# Power_supply.net
KiCad netlist of a schematic drawn in Altium Designer
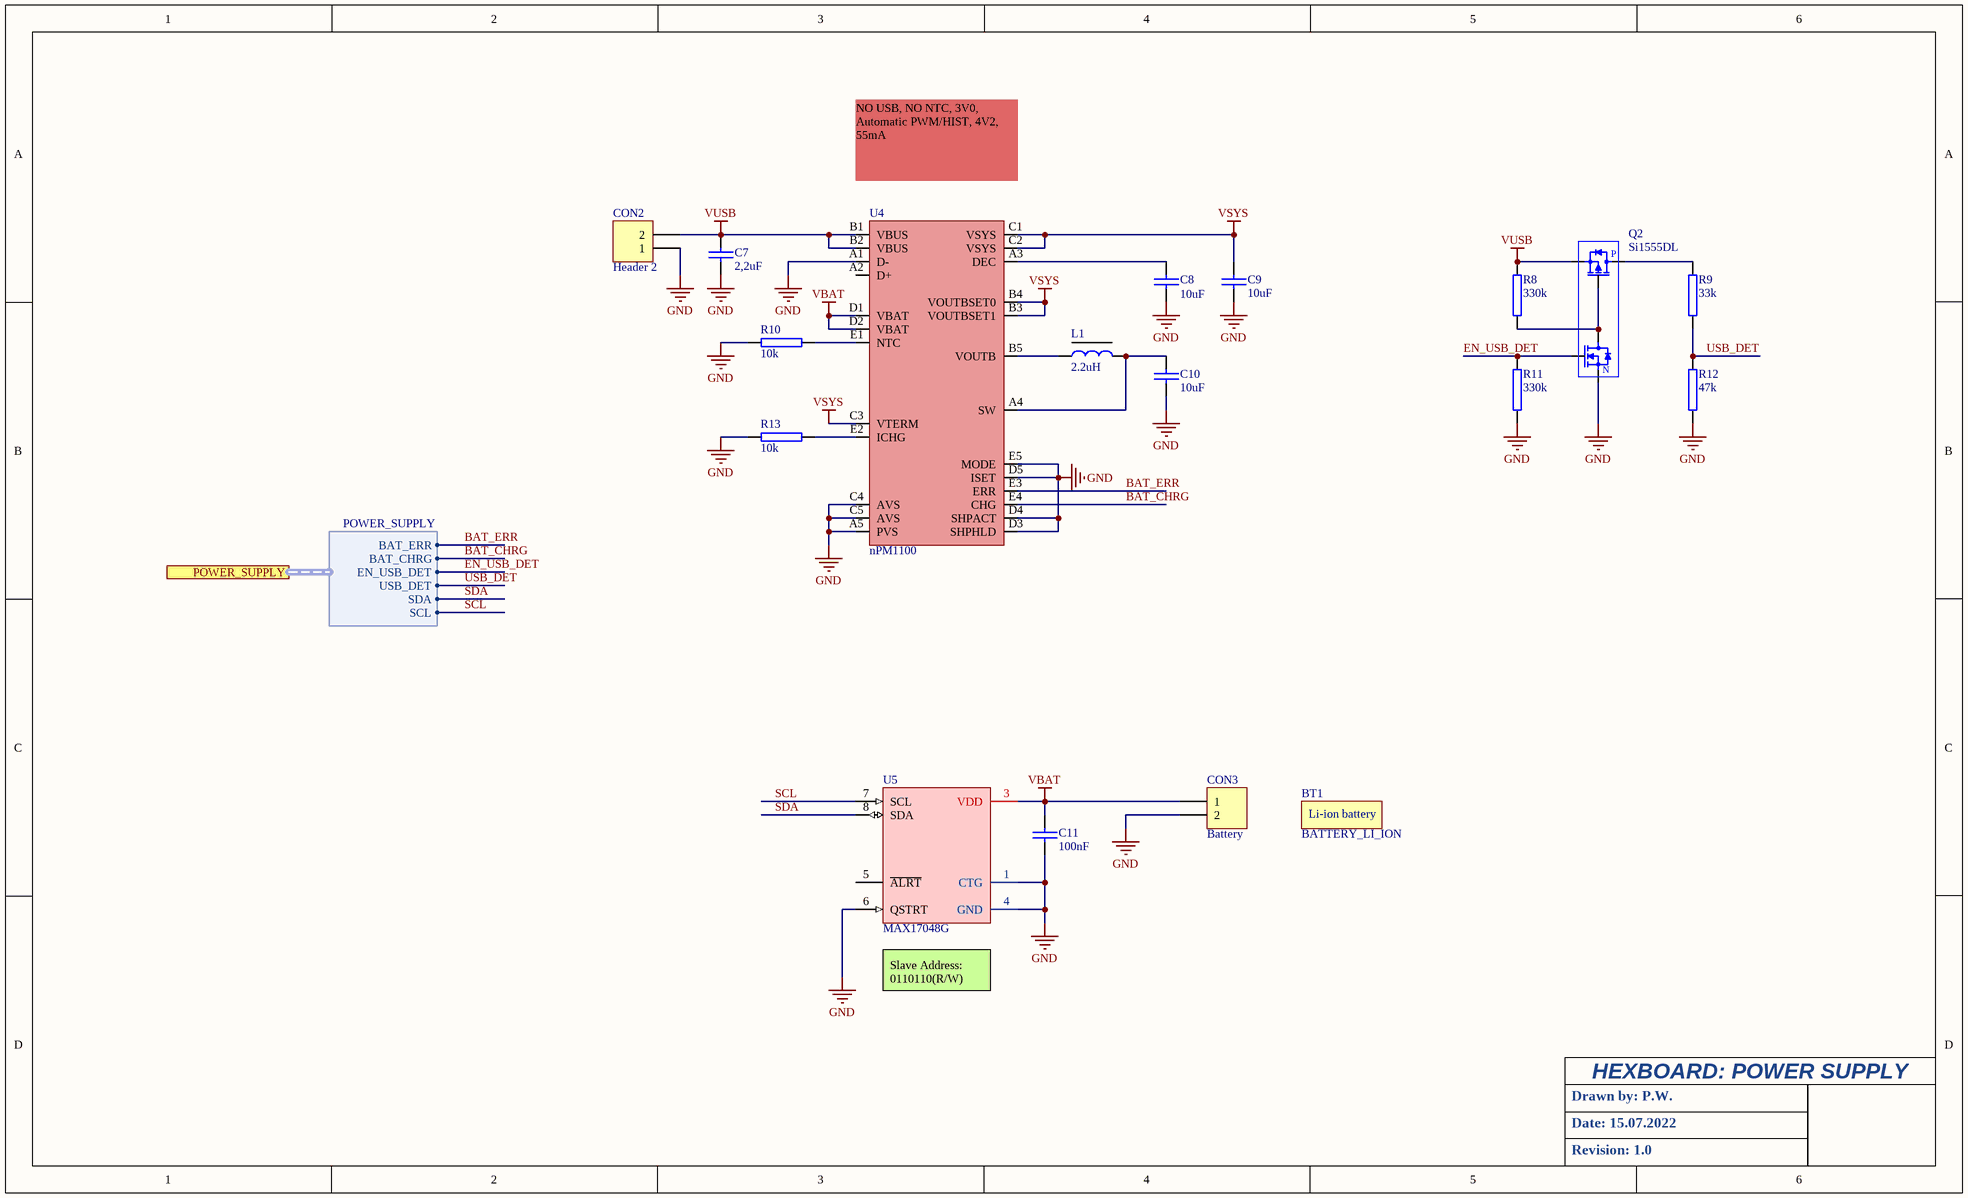
[diagram p0: Power_supply.SchDoc]

(export (version "E")
  (design (tool "Eeschema 10.0.6"))
  (components
    (comp (ref "BT1")
      (value "BATTERY_LI_ION")
      (footprint "LI-ion battery 100mAh")
      (description "Battery")
      (libsource (lib "LIB_PW") (part "BATTERY_LI_ION"))
    )
    (comp (ref "C7")
      (value "2,2uF")
      (footprint "C0603L")
      (description "Capacitor")
      (libsource (lib "LIB_PW") (part "CAP"))
    )
    (comp (ref "C8")
      (value "10uF")
      (footprint "C0603L")
      (description "Capacitor")
      (libsource (lib "LIB_PW") (part "CAP"))
    )
    (comp (ref "C9")
      (value "10uF")
      (footprint "C0603L")
      (description "Capacitor")
      (libsource (lib "LIB_PW") (part "CAP"))
    )
    (comp (ref "C10")
      (value "10uF")
      (footprint "C0603L")
      (description "Capacitor")
      (libsource (lib "LIB_PW") (part "CAP"))
    )
    (comp (ref "C11")
      (value "100nF")
      (footprint "C0603L")
      (description "Capacitor")
      (libsource (lib "LIB_PW") (part "CAP"))
    )
    (comp (ref "CON2")
      (value "Header 2")
      (footprint "HDR1X2")
      (description "Header, 2-Pin")
      (fields (field (name "PUBLISHER") "Altium Limited"))
      (libsource (lib "LIB_PW") (part "Header 2"))
    )
    (comp (ref "CON3")
      (value "Battery")
      (footprint "HDR1X2_1mm27")
      (description "Header, 2-Pin")
      (fields (field (name "PUBLISHER") "Altium Limited"))
      (libsource (lib "") (part "Header 2_1"))
    )
    (comp (ref "L1") (value "2.2uH") (footprint "L0805") (libsource (lib "SCH_PW") (part "INDUCTOR")))
    (comp (ref "Q2") (value "Si1555DL") (footprint "SOT-363") (libsource (lib "LIB_PW") (part "Si1555DL")))
    (comp (ref "R8") (value "330k") (footprint "1608[0603]") (libsource (lib "LIB_PW") (part "RES")))
    (comp (ref "R9") (value "33k") (footprint "1608[0603]") (libsource (lib "LIB_PW") (part "RES")))
    (comp (ref "R10") (value "10k") (footprint "1608[0603]") (libsource (lib "LIB_PW") (part "RES")))
    (comp (ref "R11") (value "330k") (footprint "1608[0603]") (libsource (lib "LIB_PW") (part "RES")))
    (comp (ref "R12") (value "47k") (footprint "1608[0603]") (libsource (lib "LIB_PW") (part "RES")))
    (comp (ref "R13") (value "10k") (footprint "1608[0603]") (libsource (lib "LIB_PW") (part "RES")))
    (comp (ref "U4")
      (value "nPM1100")
      (footprint "BGA25C40P5X5_207X207X52N")
      (description "Integrated Power Managment IC")
      (libsource (lib "LIB_PW") (part "nPM1100"))
    )
    (comp (ref "U5")
      (value "MAX17048G")
      (footprint "TDFN8_2x2x075")
      (description "1-Cell/2-Cell Fuel Gauge with ModelGauge")
      (libsource (lib "LIB_PW") (part "MAX17048G"))
    )
  )
  (nets
    (net (code "2") (name "/BAT_CHRG") (class "Default")
      (node (ref "U4") (pin "E4") (pinfunction "CHG_E4") (pintype "passive"))
    )
    (net (code "3") (name "/BAT_ERR") (class "Default")
      (node (ref "U4") (pin "E3") (pinfunction "ERR_E3") (pintype "passive"))
    )
    (net (code "4") (name "/EN_USB_DET") (class "Default")
      (node (ref "Q2") (pin "2") (pinfunction "G1_2") (pintype "passive"))
      (node (ref "R11") (pin "2") (pinfunction "2_2") (pintype "passive"))
    )
    (net (code "5") (name "/SCL") (class "Default")
      (node (ref "U5") (pin "7") (pinfunction "SCL_7") (pintype "input"))
    )
    (net (code "6") (name "/SDA") (class "Default")
      (node (ref "U5") (pin "8") (pinfunction "SDA_8") (pintype "bidirectional"))
    )
    (net (code "7") (name "/USB_DET") (class "Default")
      (node (ref "R12") (pin "2") (pinfunction "2_2") (pintype "passive"))
      (node (ref "R9") (pin "1") (pinfunction "1_1") (pintype "passive"))
    )
    (net (code "9") (name "GND") (class "Default")
      (node (ref "C10") (pin "2") (pinfunction "2_2") (pintype "passive"))
      (node (ref "C11") (pin "2") (pinfunction "2_2") (pintype "passive"))
      (node (ref "C7") (pin "2") (pinfunction "2_2") (pintype "passive"))
      (node (ref "C8") (pin "2") (pinfunction "2_2") (pintype "passive"))
      (node (ref "C9") (pin "2") (pinfunction "2_2") (pintype "passive"))
      (node (ref "CON2") (pin "1") (pinfunction "1_1") (pintype "passive"))
      (node (ref "CON3") (pin "2") (pinfunction "2_2") (pintype "passive"))
      (node (ref "Q2") (pin "1") (pinfunction "S1_1") (pintype "passive"))
      (node (ref "R10") (pin "2") (pinfunction "2_2") (pintype "passive"))
      (node (ref "R11") (pin "1") (pinfunction "1_1") (pintype "passive"))
      (node (ref "R12") (pin "1") (pinfunction "1_1") (pintype "passive"))
      (node (ref "R13") (pin "2") (pinfunction "2_2") (pintype "passive"))
      (node (ref "U4") (pin "A1") (pinfunction "D-_A1") (pintype "passive"))
      (node (ref "U4") (pin "A5") (pinfunction "PVS_A5") (pintype "passive"))
      (node (ref "U4") (pin "C4") (pinfunction "AVS_C4") (pintype "passive"))
      (node (ref "U4") (pin "C5") (pinfunction "AVS_C5") (pintype "passive"))
      (node (ref "U4") (pin "D3") (pinfunction "SHPHLD_D3") (pintype "passive"))
      (node (ref "U4") (pin "D4") (pinfunction "SHPACT_D4") (pintype "passive"))
      (node (ref "U4") (pin "D5") (pinfunction "ISET_D5") (pintype "passive"))
      (node (ref "U4") (pin "E5") (pinfunction "MODE_E5") (pintype "passive"))
      (node (ref "U5") (pin "1") (pinfunction "CTG_1") (pintype "power_in"))
      (node (ref "U5") (pin "4") (pinfunction "GND_4") (pintype "power_in"))
      (node (ref "U5") (pin "6") (pinfunction "QSTRT_6") (pintype "input"))
    )
    (net (code "10") (name "Net-(Q2-D1)") (class "Default")
      (node (ref "Q2") (pin "5") (pinfunction "G2_5") (pintype "passive"))
      (node (ref "Q2") (pin "6") (pinfunction "D1_6") (pintype "passive"))
      (node (ref "R8") (pin "1") (pinfunction "1_1") (pintype "passive"))
    )
    (net (code "11") (name "Net-(Q2-D2)") (class "Default")
      (node (ref "Q2") (pin "3") (pinfunction "D2_3") (pintype "passive"))
      (node (ref "R9") (pin "2") (pinfunction "2_2") (pintype "passive"))
    )
    (net (code "12") (name "Net-(U4-DEC)") (class "Default")
      (node (ref "C8") (pin "1") (pinfunction "1_1") (pintype "passive"))
      (node (ref "U4") (pin "A3") (pinfunction "DEC_A3") (pintype "passive"))
    )
    (net (code "13") (name "Net-(U4-ICHG)") (class "Default")
      (node (ref "R13") (pin "1") (pinfunction "1_1") (pintype "passive"))
      (node (ref "U4") (pin "E2") (pinfunction "ICHG_E2") (pintype "passive"))
    )
    (net (code "14") (name "Net-(U4-NTC)") (class "Default")
      (node (ref "R10") (pin "1") (pinfunction "1_1") (pintype "passive"))
      (node (ref "U4") (pin "E1") (pinfunction "NTC_E1") (pintype "passive"))
    )
    (net (code "15") (name "Net-(U4-SW)") (class "Default")
      (node (ref "C10") (pin "1") (pinfunction "1_1") (pintype "passive"))
      (node (ref "L1") (pin "2") (pinfunction "2_2") (pintype "passive"))
      (node (ref "U4") (pin "A4") (pinfunction "SW_A4") (pintype "passive"))
    )
    (net (code "16") (name "Net-(U4-VOUTB)") (class "Default")
      (node (ref "L1") (pin "1") (pinfunction "1_1") (pintype "passive"))
      (node (ref "U4") (pin "B5") (pinfunction "VOUTB_B5") (pintype "passive"))
    )
    (net (code "17") (name "VBAT") (class "Default")
      (node (ref "C11") (pin "1") (pinfunction "1_1") (pintype "passive"))
      (node (ref "CON3") (pin "1") (pinfunction "1_1") (pintype "passive"))
      (node (ref "U4") (pin "D1") (pinfunction "VBAT_D1") (pintype "passive"))
      (node (ref "U4") (pin "D2") (pinfunction "VBAT_D2") (pintype "passive"))
      (node (ref "U5") (pin "3") (pinfunction "VDD_3") (pintype "power_in"))
    )
    (net (code "18") (name "VSYS") (class "Default")
      (node (ref "C9") (pin "1") (pinfunction "1_1") (pintype "passive"))
      (node (ref "U4") (pin "B3") (pinfunction "VOUTBSET1_B3") (pintype "passive"))
      (node (ref "U4") (pin "B4") (pinfunction "VOUTBSET0_B4") (pintype "passive"))
      (node (ref "U4") (pin "C1") (pinfunction "VSYS_C1") (pintype "passive"))
      (node (ref "U4") (pin "C2") (pinfunction "VSYS_C2") (pintype "passive"))
      (node (ref "U4") (pin "C3") (pinfunction "VTERM_C3") (pintype "passive"))
    )
    (net (code "19") (name "VUSB") (class "Default")
      (node (ref "C7") (pin "1") (pinfunction "1_1") (pintype "passive"))
      (node (ref "CON2") (pin "2") (pinfunction "2_2") (pintype "passive"))
      (node (ref "Q2") (pin "4") (pinfunction "S2_4") (pintype "passive"))
      (node (ref "R8") (pin "2") (pinfunction "2_2") (pintype "passive"))
      (node (ref "U4") (pin "B1") (pinfunction "VBUS_B1") (pintype "passive"))
      (node (ref "U4") (pin "B2") (pinfunction "VBUS_B2") (pintype "passive"))
    )
    (net (code "20") (name "unconnected-(U4-D+-PadA2)") (class "Default")
      (node (ref "U4") (pin "A2") (pinfunction "D+_A2") (pintype "passive"))
    )
    (net (code "21") (name "unconnected-(U5-~{ALRT}-Pad5)") (class "Default")
      (node (ref "U5") (pin "5") (pinfunction "~{ALRT}_5") (pintype "open_collector"))
    )
  )
)
